# Connectors.net
KiCad netlist of a schematic drawn in Altium Designer
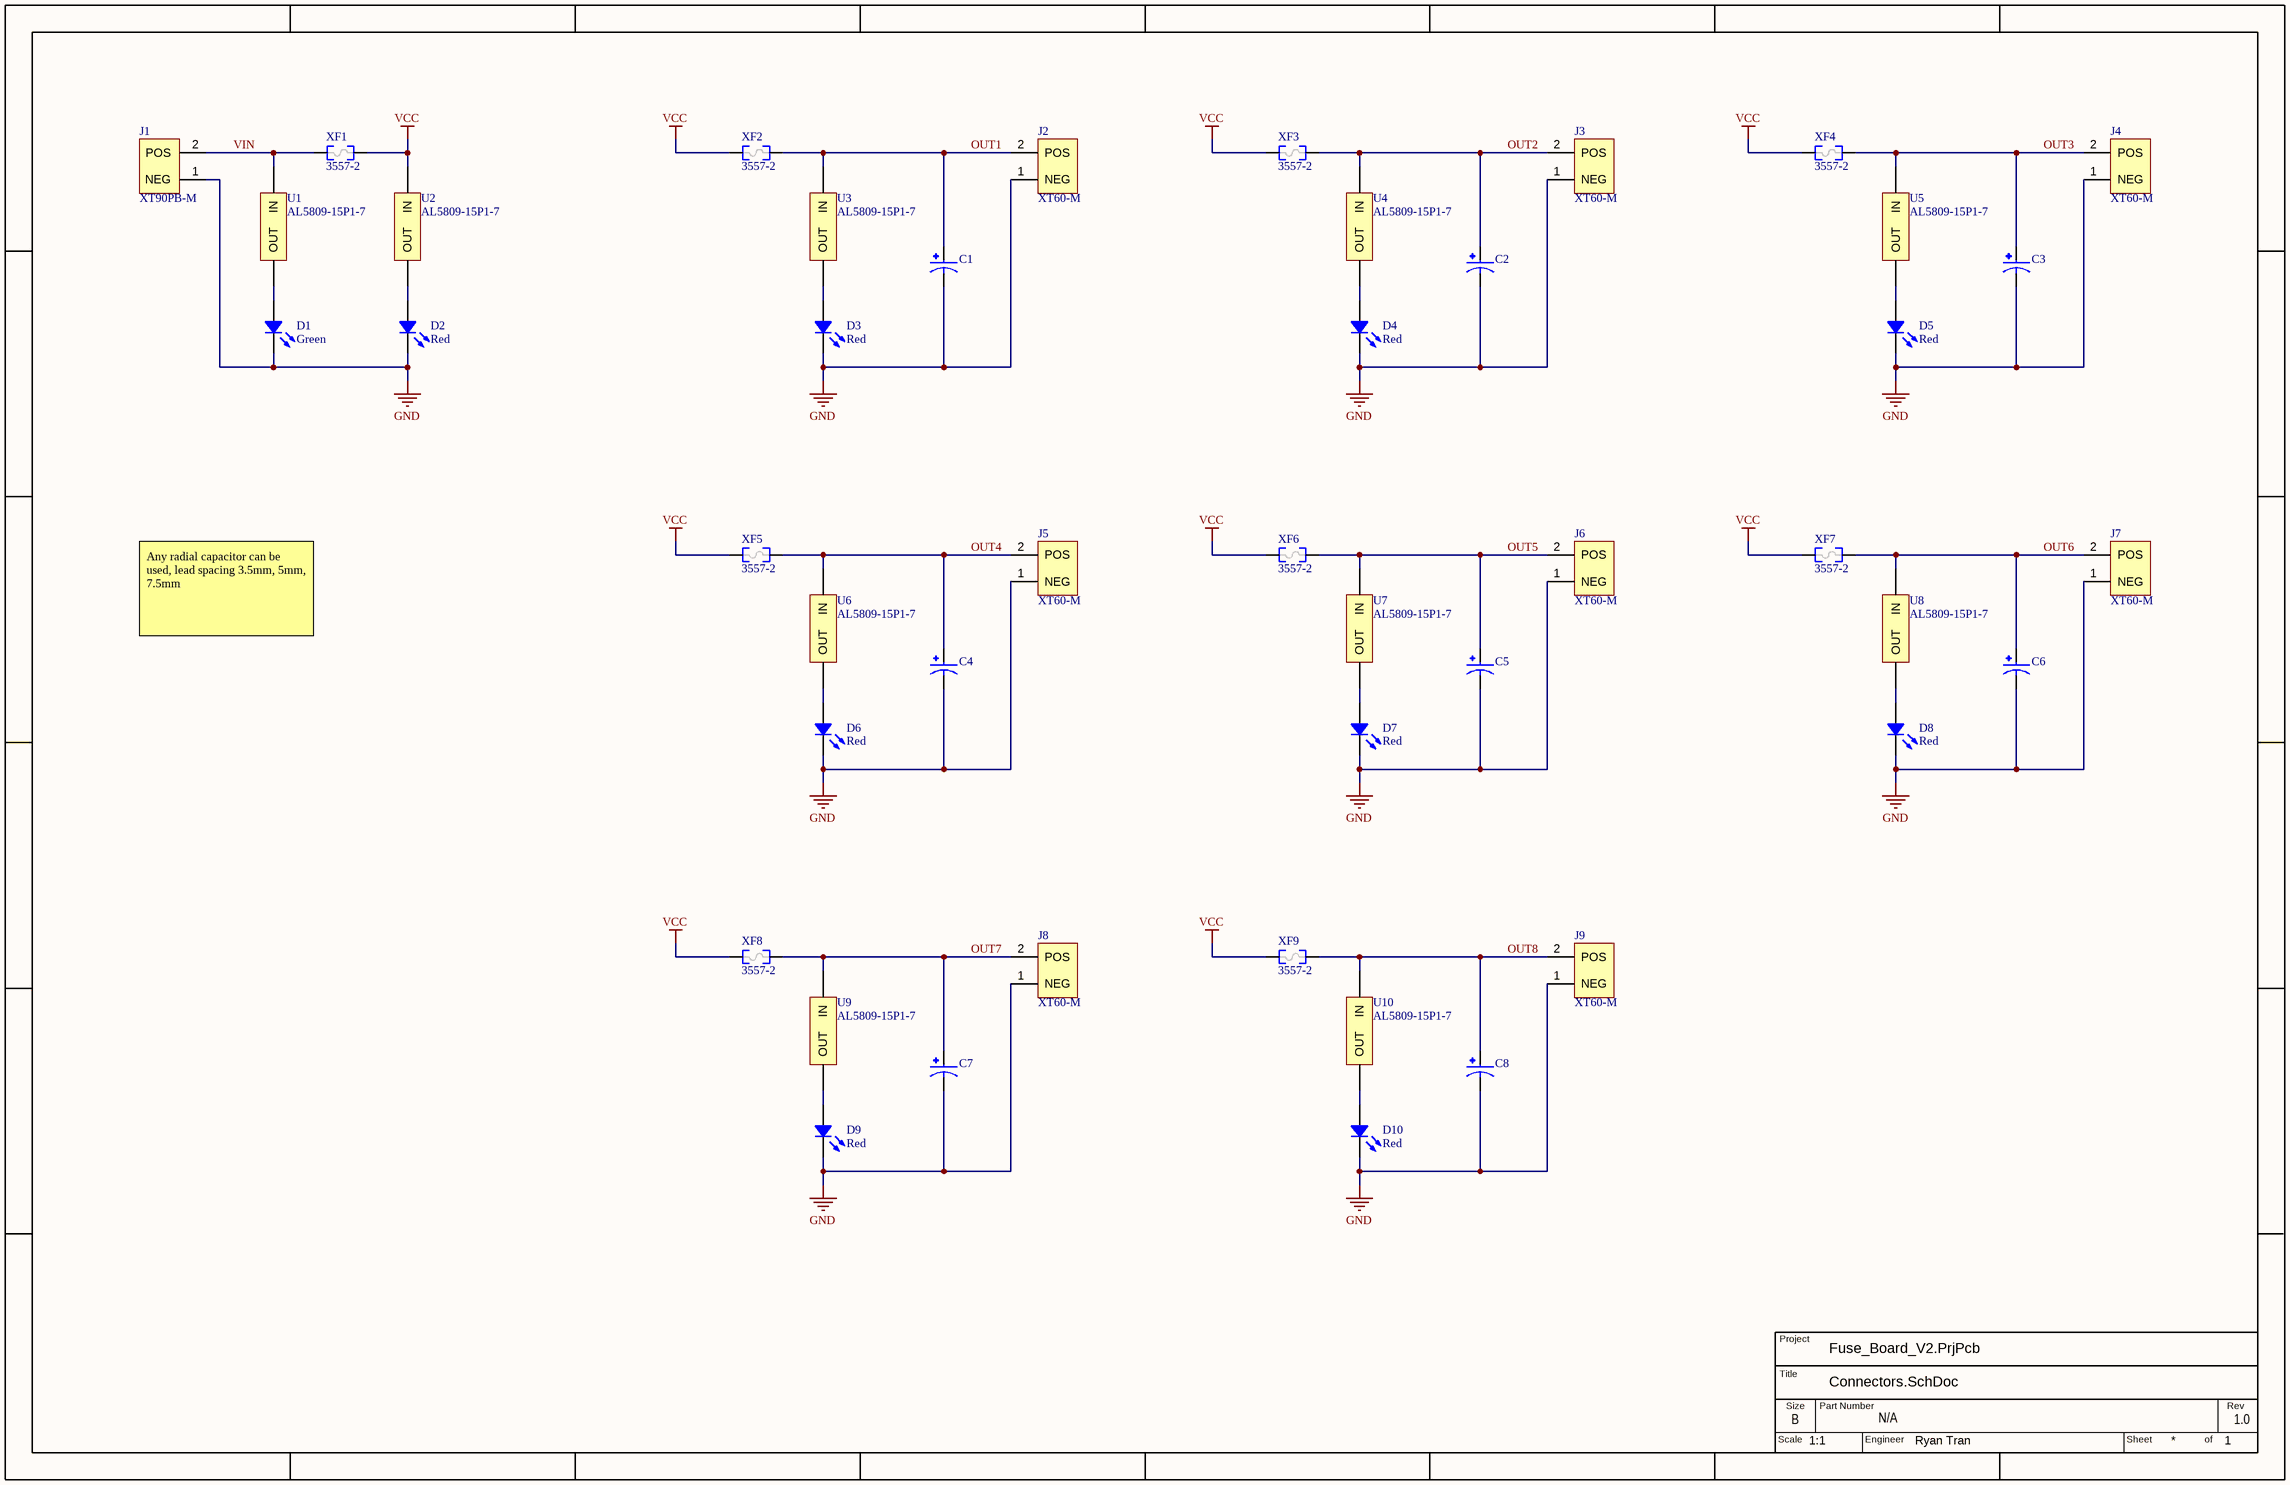
[diagram p0: Connectors.SchDoc]

(export (version "E")
  (design (tool "Eeschema 10.0.6"))
  (components
    (comp (ref "C1")
      (value "Capacitor Generic")
      (footprint "RADIAL_CAP_10mm")
      (description "Cap Radial Aluminum Cylindrical Can 3.5mm, 5mm")
      (fields (field (name "MF") "Panasonic") (field (name "MP") "ECA-2WHG220"))
      (libsource (lib "Fuse_Board_Symbols") (part "Capacitor Generic"))
    )
    (comp (ref "C2")
      (value "Capacitor Generic")
      (footprint "RADIAL_CAP_10mm")
      (description "Cap Radial Aluminum Cylindrical Can 3.5mm, 5mm")
      (fields (field (name "MF") "Panasonic") (field (name "MP") "ECA-2WHG220"))
      (libsource (lib "Fuse_Board_Symbols") (part "Capacitor Generic"))
    )
    (comp (ref "C3")
      (value "Capacitor Generic")
      (footprint "RADIAL_CAP_10mm")
      (description "Cap Radial Aluminum Cylindrical Can 3.5mm, 5mm")
      (fields (field (name "MF") "Panasonic") (field (name "MP") "ECA-2WHG220"))
      (libsource (lib "Fuse_Board_Symbols") (part "Capacitor Generic"))
    )
    (comp (ref "C4")
      (value "Capacitor Generic")
      (footprint "RADIAL_CAP_10mm")
      (description "Cap Radial Aluminum Cylindrical Can 3.5mm, 5mm")
      (fields (field (name "MF") "Panasonic") (field (name "MP") "ECA-2WHG220"))
      (libsource (lib "Fuse_Board_Symbols") (part "Capacitor Generic"))
    )
    (comp (ref "C5")
      (value "Capacitor Generic")
      (footprint "RADIAL_CAP_10mm")
      (description "Cap Radial Aluminum Cylindrical Can 3.5mm, 5mm")
      (fields (field (name "MF") "Panasonic") (field (name "MP") "ECA-2WHG220"))
      (libsource (lib "Fuse_Board_Symbols") (part "Capacitor Generic"))
    )
    (comp (ref "C6")
      (value "Capacitor Generic")
      (footprint "RADIAL_CAP_10mm")
      (description "Cap Radial Aluminum Cylindrical Can 3.5mm, 5mm")
      (fields (field (name "MF") "Panasonic") (field (name "MP") "ECA-2WHG220"))
      (libsource (lib "Fuse_Board_Symbols") (part "Capacitor Generic"))
    )
    (comp (ref "C7")
      (value "Capacitor Generic")
      (footprint "RADIAL_CAP_10mm")
      (description "Cap Radial Aluminum Cylindrical Can 3.5mm, 5mm")
      (fields (field (name "MF") "Panasonic") (field (name "MP") "ECA-2WHG220"))
      (libsource (lib "Fuse_Board_Symbols") (part "Capacitor Generic"))
    )
    (comp (ref "C8")
      (value "Capacitor Generic")
      (footprint "RADIAL_CAP_10mm")
      (description "Cap Radial Aluminum Cylindrical Can 3.5mm, 5mm")
      (fields (field (name "MF") "Panasonic") (field (name "MP") "ECA-2WHG220"))
      (libsource (lib "Fuse_Board_Symbols") (part "Capacitor Generic"))
    )
    (comp (ref "D1")
      (value "Green")
      (footprint "LED 0603_1608 GREEN")
      (description "LED GREEN CLEAR CHIP SMD")
      (fields (field (name "PART NUMBER") "LTST-C193TGKT-5A") (field (name "MANUFACTURER") "Lite-On Inc."))
      (libsource (lib "Celestial Altium Library - altium_library") (part "LED"))
    )
    (comp (ref "D2")
      (value "Red")
      (footprint "LED 0603_1608 RED")
      (description "LED RED CLEAR 2SMD")
      (fields
        (field (name "PART NUMBER") "19-217/R6C-AL1M2VY/3T")
        (field (name "MANUFACTURER") "Everlight Electronics Co Ltd")
      )
      (libsource (lib "Celestial Altium Library - altium_library") (part "LED"))
    )
    (comp (ref "D3")
      (value "Red")
      (footprint "LED 0603_1608 RED")
      (description "LED RED CLEAR 2SMD")
      (fields
        (field (name "PART NUMBER") "19-217/R6C-AL1M2VY/3T")
        (field (name "MANUFACTURER") "Everlight Electronics Co Ltd")
      )
      (libsource (lib "Celestial Altium Library - altium_library") (part "LED"))
    )
    (comp (ref "D4")
      (value "Red")
      (footprint "LED 0603_1608 RED")
      (description "LED RED CLEAR 2SMD")
      (fields
        (field (name "PART NUMBER") "19-217/R6C-AL1M2VY/3T")
        (field (name "MANUFACTURER") "Everlight Electronics Co Ltd")
      )
      (libsource (lib "Celestial Altium Library - altium_library") (part "LED"))
    )
    (comp (ref "D5")
      (value "Red")
      (footprint "LED 0603_1608 RED")
      (description "LED RED CLEAR 2SMD")
      (fields
        (field (name "PART NUMBER") "19-217/R6C-AL1M2VY/3T")
        (field (name "MANUFACTURER") "Everlight Electronics Co Ltd")
      )
      (libsource (lib "Celestial Altium Library - altium_library") (part "LED"))
    )
    (comp (ref "D6")
      (value "Red")
      (footprint "LED 0603_1608 RED")
      (description "LED RED CLEAR 2SMD")
      (fields
        (field (name "PART NUMBER") "19-217/R6C-AL1M2VY/3T")
        (field (name "MANUFACTURER") "Everlight Electronics Co Ltd")
      )
      (libsource (lib "Celestial Altium Library - altium_library") (part "LED"))
    )
    (comp (ref "D7")
      (value "Red")
      (footprint "LED 0603_1608 RED")
      (description "LED RED CLEAR 2SMD")
      (fields
        (field (name "PART NUMBER") "19-217/R6C-AL1M2VY/3T")
        (field (name "MANUFACTURER") "Everlight Electronics Co Ltd")
      )
      (libsource (lib "Celestial Altium Library - altium_library") (part "LED"))
    )
    (comp (ref "D8")
      (value "Red")
      (footprint "LED 0603_1608 RED")
      (description "LED RED CLEAR 2SMD")
      (fields
        (field (name "PART NUMBER") "19-217/R6C-AL1M2VY/3T")
        (field (name "MANUFACTURER") "Everlight Electronics Co Ltd")
      )
      (libsource (lib "Celestial Altium Library - altium_library") (part "LED"))
    )
    (comp (ref "D9")
      (value "Red")
      (footprint "LED 0603_1608 RED")
      (description "LED RED CLEAR 2SMD")
      (fields
        (field (name "PART NUMBER") "19-217/R6C-AL1M2VY/3T")
        (field (name "MANUFACTURER") "Everlight Electronics Co Ltd")
      )
      (libsource (lib "Celestial Altium Library - altium_library") (part "LED"))
    )
    (comp (ref "D10")
      (value "Red")
      (footprint "LED 0603_1608 RED")
      (description "LED RED CLEAR 2SMD")
      (fields
        (field (name "PART NUMBER") "19-217/R6C-AL1M2VY/3T")
        (field (name "MANUFACTURER") "Everlight Electronics Co Ltd")
      )
      (libsource (lib "Celestial Altium Library - altium_library") (part "LED"))
    )
    (comp (ref "J1")
      (value "XT90PB-M")
      (footprint "XT90PB-M")
      (description "Plug; DC supply; XT60; male; PIN: 2; for cable; soldered; 30A; 500V")
      (fields (field (name "MP") "XT60-M") (field (name "MF") "AMASS"))
      (libsource (lib "Fuse_Board_Symbols") (part "XT90PB-M"))
    )
    (comp (ref "J2")
      (value "XT60-M")
      (footprint "AMASS_XT60-M")
      (description "Plug; DC supply; XT60; male; PIN: 2; for cable; soldered; 30A; 500V")
      (fields (field (name "MF") "AMASS"))
      (libsource (lib "Fuse_Board_Symbols") (part "XT60-M"))
    )
    (comp (ref "J3")
      (value "XT60-M")
      (footprint "AMASS_XT60-M")
      (description "Plug; DC supply; XT60; male; PIN: 2; for cable; soldered; 30A; 500V")
      (fields (field (name "MF") "AMASS"))
      (libsource (lib "Fuse_Board_Symbols") (part "XT60-M"))
    )
    (comp (ref "J4")
      (value "XT60-M")
      (footprint "AMASS_XT60-M")
      (description "Plug; DC supply; XT60; male; PIN: 2; for cable; soldered; 30A; 500V")
      (fields (field (name "MF") "AMASS"))
      (libsource (lib "Fuse_Board_Symbols") (part "XT60-M"))
    )
    (comp (ref "J5")
      (value "XT60-M")
      (footprint "AMASS_XT60-M")
      (description "Plug; DC supply; XT60; male; PIN: 2; for cable; soldered; 30A; 500V")
      (fields (field (name "MF") "AMASS"))
      (libsource (lib "Fuse_Board_Symbols") (part "XT60-M"))
    )
    (comp (ref "J6")
      (value "XT60-M")
      (footprint "AMASS_XT60-M")
      (description "Plug; DC supply; XT60; male; PIN: 2; for cable; soldered; 30A; 500V")
      (fields (field (name "MF") "AMASS"))
      (libsource (lib "Fuse_Board_Symbols") (part "XT60-M"))
    )
    (comp (ref "J7")
      (value "XT60-M")
      (footprint "AMASS_XT60-M")
      (description "Plug; DC supply; XT60; male; PIN: 2; for cable; soldered; 30A; 500V")
      (fields (field (name "MF") "AMASS"))
      (libsource (lib "Fuse_Board_Symbols") (part "XT60-M"))
    )
    (comp (ref "J8")
      (value "XT60-M")
      (footprint "AMASS_XT60-M")
      (description "Plug; DC supply; XT60; male; PIN: 2; for cable; soldered; 30A; 500V")
      (fields (field (name "MF") "AMASS"))
      (libsource (lib "Fuse_Board_Symbols") (part "XT60-M"))
    )
    (comp (ref "J9")
      (value "XT60-M")
      (footprint "AMASS_XT60-M")
      (description "Plug; DC supply; XT60; male; PIN: 2; for cable; soldered; 30A; 500V")
      (fields (field (name "MF") "AMASS"))
      (libsource (lib "Fuse_Board_Symbols") (part "XT60-M"))
    )
    (comp (ref "U1")
      (value "AL5809-15P1-7")
      (footprint "POWERDI_123")
      (description "LED Driver IC 1 Output Linear - PWM Dimming 15mA PowerDI™ 123")
      (libsource (lib "Fuse_Board_Symbols") (part "AL5809-15P1-7"))
    )
    (comp (ref "U2")
      (value "AL5809-15P1-7")
      (footprint "POWERDI_123")
      (description "LED Driver IC 1 Output Linear - PWM Dimming 15mA PowerDI™ 123")
      (libsource (lib "Fuse_Board_Symbols") (part "AL5809-15P1-7"))
    )
    (comp (ref "U3")
      (value "AL5809-15P1-7")
      (footprint "POWERDI_123")
      (description "LED Driver IC 1 Output Linear - PWM Dimming 15mA PowerDI™ 123")
      (libsource (lib "Fuse_Board_Symbols") (part "AL5809-15P1-7"))
    )
    (comp (ref "U4")
      (value "AL5809-15P1-7")
      (footprint "POWERDI_123")
      (description "LED Driver IC 1 Output Linear - PWM Dimming 15mA PowerDI™ 123")
      (libsource (lib "Fuse_Board_Symbols") (part "AL5809-15P1-7"))
    )
    (comp (ref "U5")
      (value "AL5809-15P1-7")
      (footprint "POWERDI_123")
      (description "LED Driver IC 1 Output Linear - PWM Dimming 15mA PowerDI™ 123")
      (libsource (lib "Fuse_Board_Symbols") (part "AL5809-15P1-7"))
    )
    (comp (ref "U6")
      (value "AL5809-15P1-7")
      (footprint "POWERDI_123")
      (description "LED Driver IC 1 Output Linear - PWM Dimming 15mA PowerDI™ 123")
      (libsource (lib "Fuse_Board_Symbols") (part "AL5809-15P1-7"))
    )
    (comp (ref "U7")
      (value "AL5809-15P1-7")
      (footprint "POWERDI_123")
      (description "LED Driver IC 1 Output Linear - PWM Dimming 15mA PowerDI™ 123")
      (libsource (lib "Fuse_Board_Symbols") (part "AL5809-15P1-7"))
    )
    (comp (ref "U8")
      (value "AL5809-15P1-7")
      (footprint "POWERDI_123")
      (description "LED Driver IC 1 Output Linear - PWM Dimming 15mA PowerDI™ 123")
      (libsource (lib "Fuse_Board_Symbols") (part "AL5809-15P1-7"))
    )
    (comp (ref "U9")
      (value "AL5809-15P1-7")
      (footprint "POWERDI_123")
      (description "LED Driver IC 1 Output Linear - PWM Dimming 15mA PowerDI™ 123")
      (libsource (lib "Fuse_Board_Symbols") (part "AL5809-15P1-7"))
    )
    (comp (ref "U10")
      (value "AL5809-15P1-7")
      (footprint "POWERDI_123")
      (description "LED Driver IC 1 Output Linear - PWM Dimming 15mA PowerDI™ 123")
      (libsource (lib "Fuse_Board_Symbols") (part "AL5809-15P1-7"))
    )
    (comp (ref "XF1")
      (value "3557-2")
      (footprint "FUSE_3557-2")
      (description "Fuse Block 30A 500V 1 Circuit Blade Through Hole")
      (fields (field (name "MF") "Keystone Electronics"))
      (libsource (lib "XT60-30_Fuse_Board_Symbols") (part "3557-2"))
    )
    (comp (ref "XF2")
      (value "3557-2")
      (footprint "FUSE_3557-2")
      (description "Fuse Block 30A 500V 1 Circuit Blade Through Hole")
      (fields (field (name "MF") "Keystone Electronics"))
      (libsource (lib "XT60-30_Fuse_Board_Symbols") (part "3557-2"))
    )
    (comp (ref "XF3")
      (value "3557-2")
      (footprint "FUSE_3557-2")
      (description "Fuse Block 30A 500V 1 Circuit Blade Through Hole")
      (fields (field (name "MF") "Keystone Electronics"))
      (libsource (lib "XT60-30_Fuse_Board_Symbols") (part "3557-2"))
    )
    (comp (ref "XF4")
      (value "3557-2")
      (footprint "FUSE_3557-2")
      (description "Fuse Block 30A 500V 1 Circuit Blade Through Hole")
      (fields (field (name "MF") "Keystone Electronics"))
      (libsource (lib "XT60-30_Fuse_Board_Symbols") (part "3557-2"))
    )
    (comp (ref "XF5")
      (value "3557-2")
      (footprint "FUSE_3557-2")
      (description "Fuse Block 30A 500V 1 Circuit Blade Through Hole")
      (fields (field (name "MF") "Keystone Electronics"))
      (libsource (lib "XT60-30_Fuse_Board_Symbols") (part "3557-2"))
    )
    (comp (ref "XF6")
      (value "3557-2")
      (footprint "FUSE_3557-2")
      (description "Fuse Block 30A 500V 1 Circuit Blade Through Hole")
      (fields (field (name "MF") "Keystone Electronics"))
      (libsource (lib "XT60-30_Fuse_Board_Symbols") (part "3557-2"))
    )
    (comp (ref "XF7")
      (value "3557-2")
      (footprint "FUSE_3557-2")
      (description "Fuse Block 30A 500V 1 Circuit Blade Through Hole")
      (fields (field (name "MF") "Keystone Electronics"))
      (libsource (lib "XT60-30_Fuse_Board_Symbols") (part "3557-2"))
    )
    (comp (ref "XF8")
      (value "3557-2")
      (footprint "FUSE_3557-2")
      (description "Fuse Block 30A 500V 1 Circuit Blade Through Hole")
      (fields (field (name "MF") "Keystone Electronics"))
      (libsource (lib "XT60-30_Fuse_Board_Symbols") (part "3557-2"))
    )
    (comp (ref "XF9")
      (value "3557-2")
      (footprint "FUSE_3557-2")
      (description "Fuse Block 30A 500V 1 Circuit Blade Through Hole")
      (fields (field (name "MF") "Keystone Electronics"))
      (libsource (lib "XT60-30_Fuse_Board_Symbols") (part "3557-2"))
    )
  )
  (nets
    (net (code "1") (name "/OUT1") (class "Default")
      (node (ref "C1") (pin "2") (pinfunction "2_2") (pintype "passive"))
      (node (ref "J2") (pin "2") (pinfunction "POS_2") (pintype "passive"))
      (node (ref "U3") (pin "1") (pinfunction "IN_1") (pintype "passive"))
      (node (ref "XF2") (pin "2") (pinfunction "2_2") (pintype "passive"))
    )
    (net (code "2") (name "/OUT2") (class "Default")
      (node (ref "C2") (pin "2") (pinfunction "2_2") (pintype "passive"))
      (node (ref "J3") (pin "2") (pinfunction "POS_2") (pintype "passive"))
      (node (ref "U4") (pin "1") (pinfunction "IN_1") (pintype "passive"))
      (node (ref "XF3") (pin "2") (pinfunction "2_2") (pintype "passive"))
    )
    (net (code "3") (name "/OUT3") (class "Default")
      (node (ref "C3") (pin "2") (pinfunction "2_2") (pintype "passive"))
      (node (ref "J4") (pin "2") (pinfunction "POS_2") (pintype "passive"))
      (node (ref "U5") (pin "1") (pinfunction "IN_1") (pintype "passive"))
      (node (ref "XF4") (pin "2") (pinfunction "2_2") (pintype "passive"))
    )
    (net (code "4") (name "/OUT4") (class "Default")
      (node (ref "C4") (pin "2") (pinfunction "2_2") (pintype "passive"))
      (node (ref "J5") (pin "2") (pinfunction "POS_2") (pintype "passive"))
      (node (ref "U6") (pin "1") (pinfunction "IN_1") (pintype "passive"))
      (node (ref "XF5") (pin "2") (pinfunction "2_2") (pintype "passive"))
    )
    (net (code "5") (name "/OUT5") (class "Default")
      (node (ref "C5") (pin "2") (pinfunction "2_2") (pintype "passive"))
      (node (ref "J6") (pin "2") (pinfunction "POS_2") (pintype "passive"))
      (node (ref "U7") (pin "1") (pinfunction "IN_1") (pintype "passive"))
      (node (ref "XF6") (pin "2") (pinfunction "2_2") (pintype "passive"))
    )
    (net (code "6") (name "/OUT6") (class "Default")
      (node (ref "C6") (pin "2") (pinfunction "2_2") (pintype "passive"))
      (node (ref "J7") (pin "2") (pinfunction "POS_2") (pintype "passive"))
      (node (ref "U8") (pin "1") (pinfunction "IN_1") (pintype "passive"))
      (node (ref "XF7") (pin "2") (pinfunction "2_2") (pintype "passive"))
    )
    (net (code "7") (name "/OUT7") (class "Default")
      (node (ref "C7") (pin "2") (pinfunction "2_2") (pintype "passive"))
      (node (ref "J8") (pin "2") (pinfunction "POS_2") (pintype "passive"))
      (node (ref "U9") (pin "1") (pinfunction "IN_1") (pintype "passive"))
      (node (ref "XF8") (pin "2") (pinfunction "2_2") (pintype "passive"))
    )
    (net (code "8") (name "/OUT8") (class "Default")
      (node (ref "C8") (pin "2") (pinfunction "2_2") (pintype "passive"))
      (node (ref "J9") (pin "2") (pinfunction "POS_2") (pintype "passive"))
      (node (ref "U10") (pin "1") (pinfunction "IN_1") (pintype "passive"))
      (node (ref "XF9") (pin "2") (pinfunction "2_2") (pintype "passive"))
    )
    (net (code "9") (name "/VIN") (class "Default")
      (node (ref "J1") (pin "2") (pinfunction "POS_2") (pintype "passive"))
      (node (ref "U1") (pin "1") (pinfunction "IN_1") (pintype "passive"))
      (node (ref "XF1") (pin "1") (pinfunction "1_1") (pintype "passive"))
    )
    (net (code "10") (name "GND") (class "Default")
      (node (ref "C1") (pin "1") (pinfunction "1_1") (pintype "passive"))
      (node (ref "C2") (pin "1") (pinfunction "1_1") (pintype "passive"))
      (node (ref "C3") (pin "1") (pinfunction "1_1") (pintype "passive"))
      (node (ref "C4") (pin "1") (pinfunction "1_1") (pintype "passive"))
      (node (ref "C5") (pin "1") (pinfunction "1_1") (pintype "passive"))
      (node (ref "C6") (pin "1") (pinfunction "1_1") (pintype "passive"))
      (node (ref "C7") (pin "1") (pinfunction "1_1") (pintype "passive"))
      (node (ref "C8") (pin "1") (pinfunction "1_1") (pintype "passive"))
      (node (ref "D1") (pin "2") (pinfunction "2_2") (pintype "passive"))
      (node (ref "D10") (pin "2") (pinfunction "2_2") (pintype "passive"))
      (node (ref "D2") (pin "2") (pinfunction "2_2") (pintype "passive"))
      (node (ref "D3") (pin "2") (pinfunction "2_2") (pintype "passive"))
      (node (ref "D4") (pin "2") (pinfunction "2_2") (pintype "passive"))
      (node (ref "D5") (pin "2") (pinfunction "2_2") (pintype "passive"))
      (node (ref "D6") (pin "2") (pinfunction "2_2") (pintype "passive"))
      (node (ref "D7") (pin "2") (pinfunction "2_2") (pintype "passive"))
      (node (ref "D8") (pin "2") (pinfunction "2_2") (pintype "passive"))
      (node (ref "D9") (pin "2") (pinfunction "2_2") (pintype "passive"))
      (node (ref "J1") (pin "1") (pinfunction "NEG_1") (pintype "passive"))
      (node (ref "J2") (pin "1") (pinfunction "NEG_1") (pintype "passive"))
      (node (ref "J3") (pin "1") (pinfunction "NEG_1") (pintype "passive"))
      (node (ref "J4") (pin "1") (pinfunction "NEG_1") (pintype "passive"))
      (node (ref "J5") (pin "1") (pinfunction "NEG_1") (pintype "passive"))
      (node (ref "J6") (pin "1") (pinfunction "NEG_1") (pintype "passive"))
      (node (ref "J7") (pin "1") (pinfunction "NEG_1") (pintype "passive"))
      (node (ref "J8") (pin "1") (pinfunction "NEG_1") (pintype "passive"))
      (node (ref "J9") (pin "1") (pinfunction "NEG_1") (pintype "passive"))
    )
    (net (code "11") (name "Net-(U1-OUT)") (class "Default")
      (node (ref "D1") (pin "1") (pinfunction "1_1") (pintype "passive"))
      (node (ref "U1") (pin "2") (pinfunction "OUT_2") (pintype "passive"))
    )
    (net (code "12") (name "Net-(U2-OUT)") (class "Default")
      (node (ref "D2") (pin "1") (pinfunction "1_1") (pintype "passive"))
      (node (ref "U2") (pin "2") (pinfunction "OUT_2") (pintype "passive"))
    )
    (net (code "13") (name "Net-(U3-OUT)") (class "Default")
      (node (ref "D3") (pin "1") (pinfunction "1_1") (pintype "passive"))
      (node (ref "U3") (pin "2") (pinfunction "OUT_2") (pintype "passive"))
    )
    (net (code "14") (name "Net-(U4-OUT)") (class "Default")
      (node (ref "D4") (pin "1") (pinfunction "1_1") (pintype "passive"))
      (node (ref "U4") (pin "2") (pinfunction "OUT_2") (pintype "passive"))
    )
    (net (code "15") (name "Net-(U5-OUT)") (class "Default")
      (node (ref "D5") (pin "1") (pinfunction "1_1") (pintype "passive"))
      (node (ref "U5") (pin "2") (pinfunction "OUT_2") (pintype "passive"))
    )
    (net (code "16") (name "Net-(U6-OUT)") (class "Default")
      (node (ref "D6") (pin "1") (pinfunction "1_1") (pintype "passive"))
      (node (ref "U6") (pin "2") (pinfunction "OUT_2") (pintype "passive"))
    )
    (net (code "17") (name "Net-(U7-OUT)") (class "Default")
      (node (ref "D7") (pin "1") (pinfunction "1_1") (pintype "passive"))
      (node (ref "U7") (pin "2") (pinfunction "OUT_2") (pintype "passive"))
    )
    (net (code "18") (name "Net-(U8-OUT)") (class "Default")
      (node (ref "D8") (pin "1") (pinfunction "1_1") (pintype "passive"))
      (node (ref "U8") (pin "2") (pinfunction "OUT_2") (pintype "passive"))
    )
    (net (code "19") (name "Net-(U9-OUT)") (class "Default")
      (node (ref "D9") (pin "1") (pinfunction "1_1") (pintype "passive"))
      (node (ref "U9") (pin "2") (pinfunction "OUT_2") (pintype "passive"))
    )
    (net (code "20") (name "Net-(U10-OUT)") (class "Default")
      (node (ref "D10") (pin "1") (pinfunction "1_1") (pintype "passive"))
      (node (ref "U10") (pin "2") (pinfunction "OUT_2") (pintype "passive"))
    )
    (net (code "21") (name "VCC") (class "Default")
      (node (ref "U2") (pin "1") (pinfunction "IN_1") (pintype "passive"))
      (node (ref "XF1") (pin "2") (pinfunction "2_2") (pintype "passive"))
      (node (ref "XF2") (pin "1") (pinfunction "1_1") (pintype "passive"))
      (node (ref "XF3") (pin "1") (pinfunction "1_1") (pintype "passive"))
      (node (ref "XF4") (pin "1") (pinfunction "1_1") (pintype "passive"))
      (node (ref "XF5") (pin "1") (pinfunction "1_1") (pintype "passive"))
      (node (ref "XF6") (pin "1") (pinfunction "1_1") (pintype "passive"))
      (node (ref "XF7") (pin "1") (pinfunction "1_1") (pintype "passive"))
      (node (ref "XF8") (pin "1") (pinfunction "1_1") (pintype "passive"))
      (node (ref "XF9") (pin "1") (pinfunction "1_1") (pintype "passive"))
    )
  )
)
